# SOC_LOGIC.net
KiCad netlist of a schematic drawn in Altium Designer
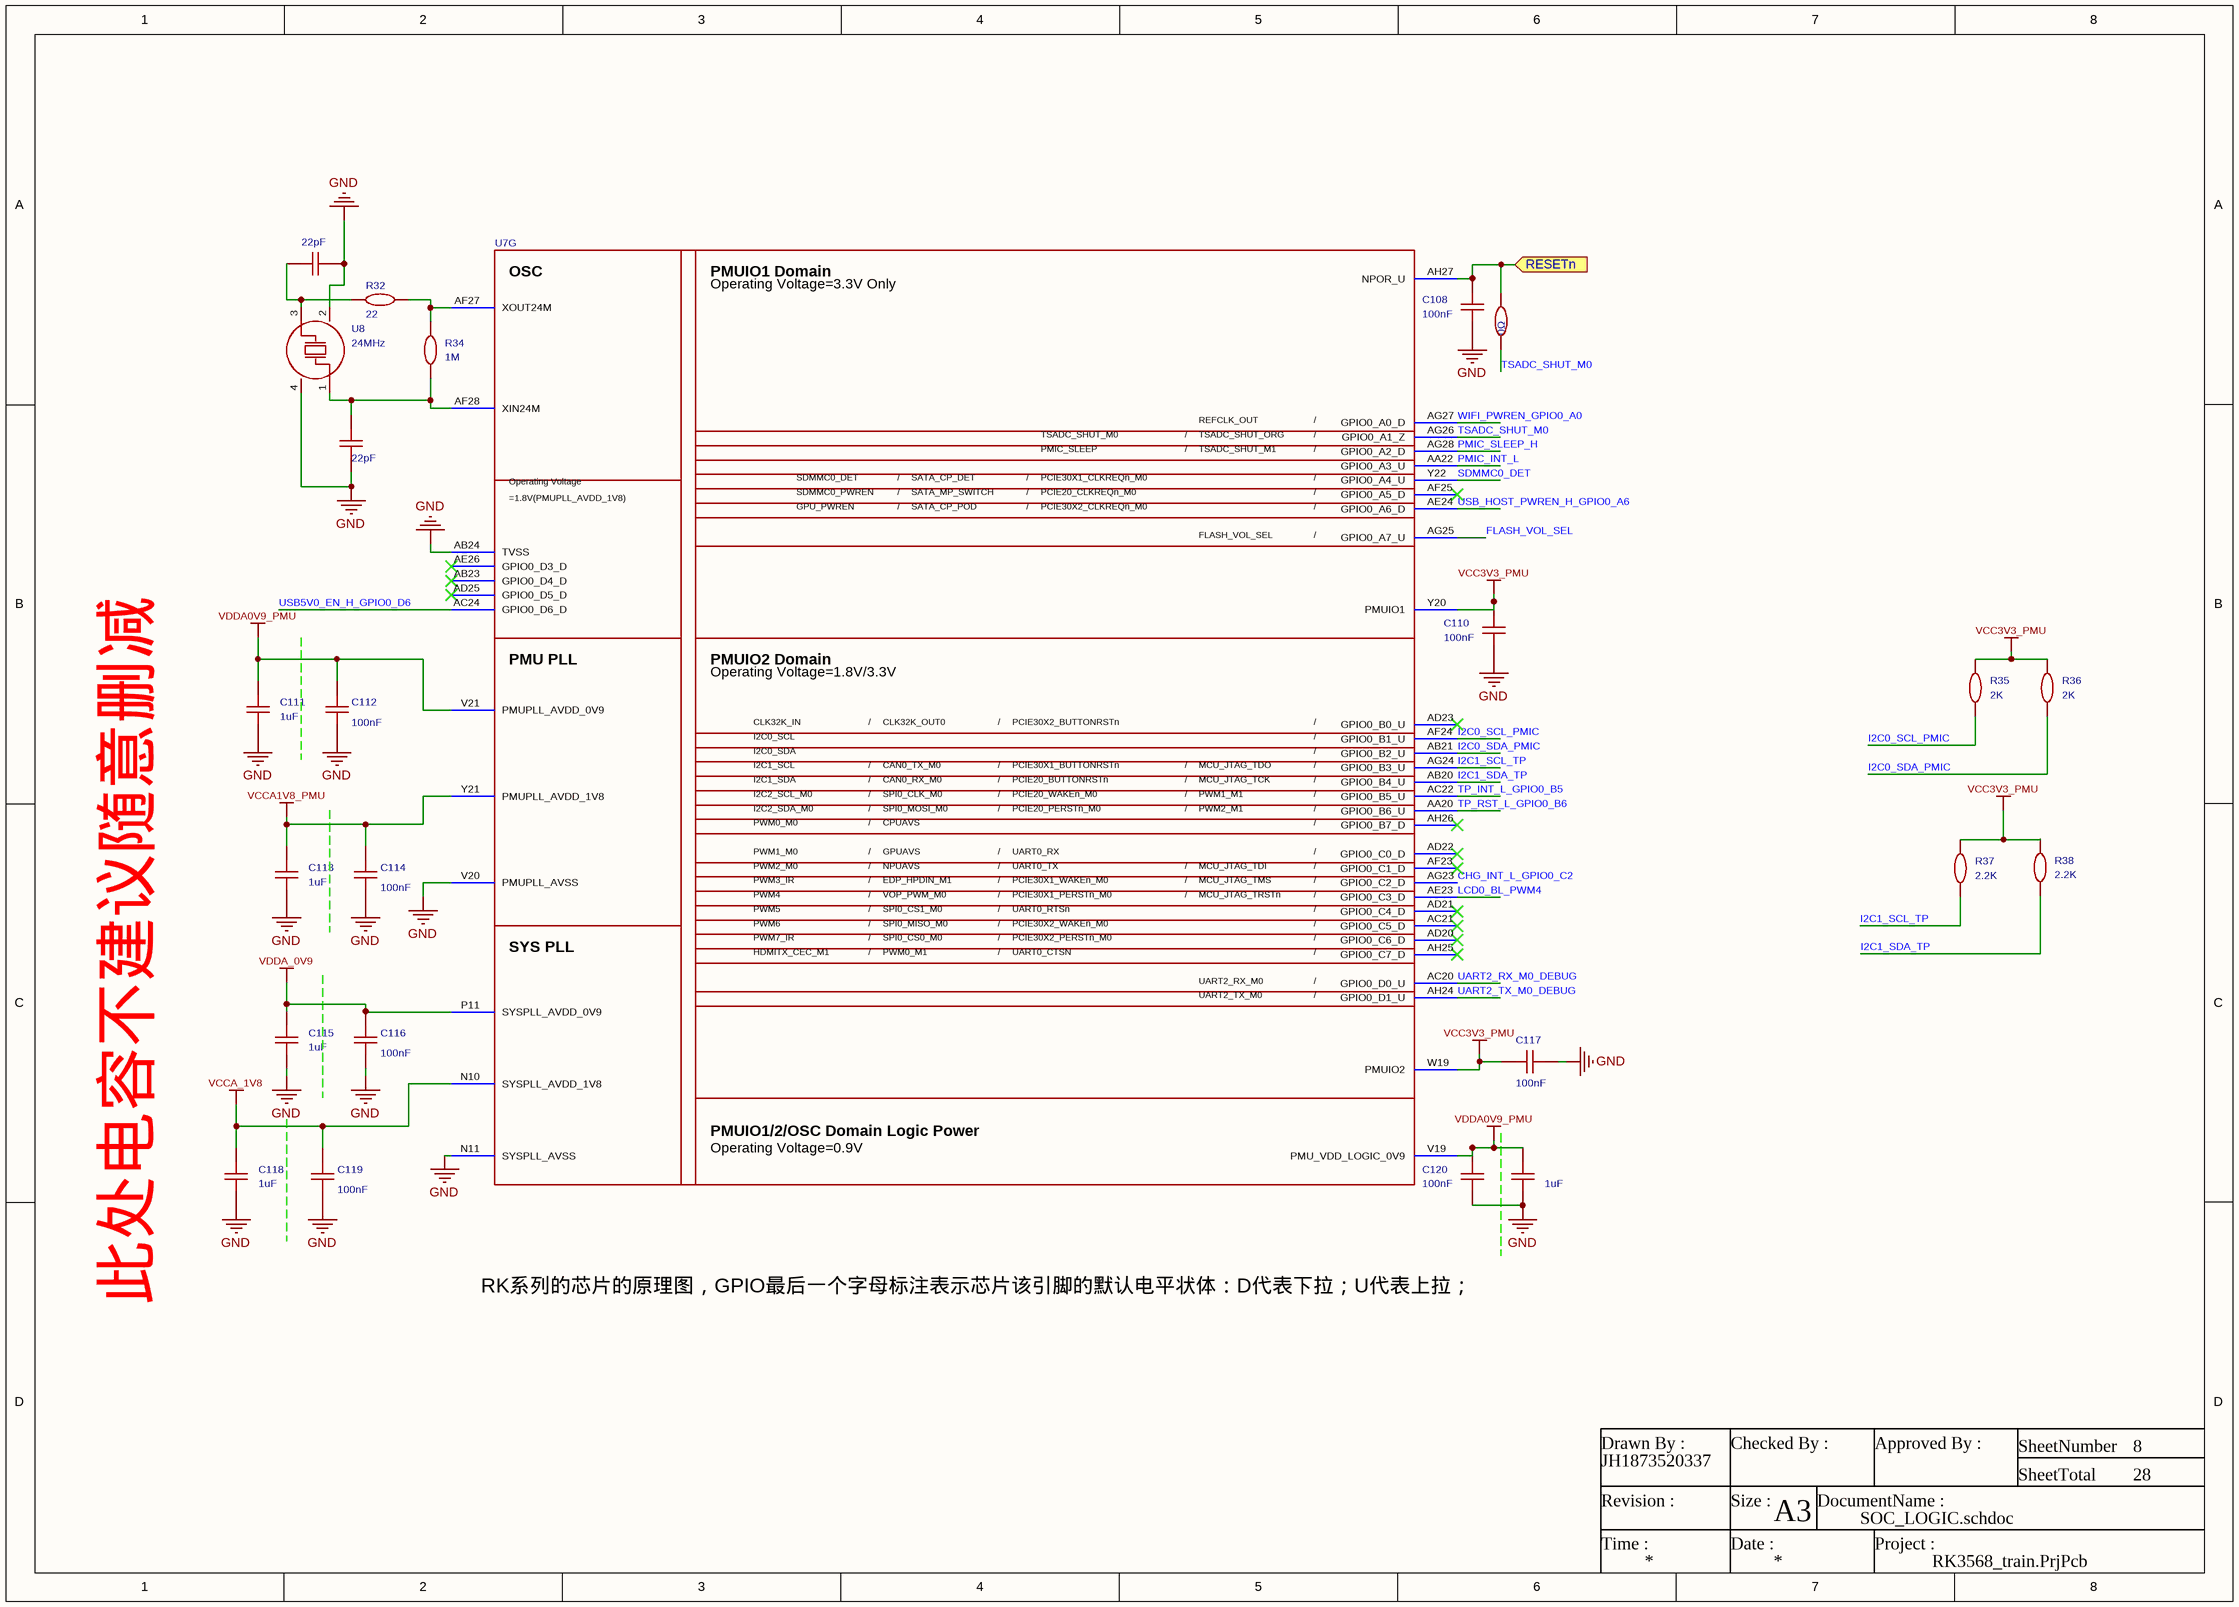
[diagram p0: SOC_LOGIC.schdoc]

(export (version "E")
  (design (tool "Eeschema 10.0.6"))
  (components
    (comp (ref "C107")
      (value "22pF")
      (footprint "MYC0402")
      (description "容值:12pF;精度:±5%;额定电压:50V;材质(温度系数):C0G;")
      (fields (field (name "MANUFACTURER") "SAMSUNG(三星)") (field (name "MANUFACTURERPART") "CL10C120JB8NNNC"))
      (libsource (lib "altium-import") (part "root_0_CL10C120JB8NNNC_"))
    )
    (comp (ref "C108")
      (value "100nF")
      (footprint "C0201")
      (description "容值:4.7uF;精度:±20%;额定电压:6.3V;温度系数:X5R;")
      (fields
        (field (name "MANUFACTURER") "muRata(村田)")
        (field (name "MANUFACTURERPART") "GRM035R60J475ME15D")
      )
      (libsource (lib "altium-import") (part "root_0_GRM035R60J475ME15D_"))
    )
    (comp (ref "C109")
      (value "22pF")
      (footprint "MYC0402")
      (description "容值:12pF;精度:±5%;额定电压:50V;材质(温度系数):C0G;")
      (fields (field (name "MANUFACTURER") "SAMSUNG(三星)") (field (name "MANUFACTURERPART") "CL10C120JB8NNNC"))
      (libsource (lib "altium-import") (part "root_1_CL10C120JB8NNNC_"))
    )
    (comp (ref "C110")
      (value "100nF")
      (footprint "C0201")
      (description "容值:4.7uF;精度:±20%;额定电压:6.3V;温度系数:X5R;")
      (fields
        (field (name "MANUFACTURER") "muRata(村田)")
        (field (name "MANUFACTURERPART") "GRM035R60J475ME15D")
      )
      (libsource (lib "altium-import") (part "root_0_GRM035R60J475ME15D_"))
    )
    (comp (ref "C111")
      (value "1uF")
      (footprint "MYC0402")
      (description "容值:1uF;精度:±10%;额定电压:50V;材质(温度系数):X5R;")
      (fields (field (name "MANUFACTURER") "SAMSUNG(三星)") (field (name "MANUFACTURERPART") "CL10A105KB8NNNC"))
      (libsource (lib "altium-import") (part "root_1_CL10A105KB8NNNC_"))
    )
    (comp (ref "C112")
      (value "100nF")
      (footprint "C0201")
      (description "容值:4.7uF;精度:±20%;额定电压:6.3V;温度系数:X5R;")
      (fields
        (field (name "MANUFACTURER") "muRata(村田)")
        (field (name "MANUFACTURERPART") "GRM035R60J475ME15D")
      )
      (libsource (lib "altium-import") (part "root_0_GRM035R60J475ME15D_"))
    )
    (comp (ref "C113")
      (value "1uF")
      (footprint "MYC0402")
      (description "容值:1uF;精度:±10%;额定电压:50V;材质(温度系数):X5R;")
      (fields (field (name "MANUFACTURER") "SAMSUNG(三星)") (field (name "MANUFACTURERPART") "CL10A105KB8NNNC"))
      (libsource (lib "altium-import") (part "root_1_CL10A105KB8NNNC_"))
    )
    (comp (ref "C114")
      (value "100nF")
      (footprint "C0201")
      (description "容值:4.7uF;精度:±20%;额定电压:6.3V;温度系数:X5R;")
      (fields
        (field (name "MANUFACTURER") "muRata(村田)")
        (field (name "MANUFACTURERPART") "GRM035R60J475ME15D")
      )
      (libsource (lib "altium-import") (part "root_0_GRM035R60J475ME15D_"))
    )
    (comp (ref "C115")
      (value "1uF")
      (footprint "MYC0402")
      (description "容值:100nF;精度:±10%;额定电压:50V;材质(温度系数):X7R;")
      (fields (field (name "MANUFACTURER") "SAMSUNG(三星)") (field (name "MANUFACTURERPART") "CL05B104KB54PNC"))
      (libsource (lib "altium-import") (part "root_1_CL05B104KB54PNC_"))
    )
    (comp (ref "C116")
      (value "100nF")
      (footprint "C0201")
      (description "容值:4.7uF;精度:±20%;额定电压:6.3V;温度系数:X5R;")
      (fields
        (field (name "MANUFACTURER") "muRata(村田)")
        (field (name "MANUFACTURERPART") "GRM035R60J475ME15D")
      )
      (libsource (lib "altium-import") (part "root_0_GRM035R60J475ME15D_"))
    )
    (comp (ref "C117")
      (value "100nF")
      (footprint "C0201")
      (description "容值:4.7uF;精度:±20%;额定电压:6.3V;温度系数:X5R;")
      (fields
        (field (name "MANUFACTURER") "muRata(村田)")
        (field (name "MANUFACTURERPART") "GRM035R60J475ME15D")
      )
      (libsource (lib "altium-import") (part "root_1_GRM035R60J475ME15D_"))
    )
    (comp (ref "C118")
      (value "1uF")
      (footprint "MYC0402")
      (description "容值:100nF;精度:±10%;额定电压:50V;材质(温度系数):X7R;")
      (fields (field (name "MANUFACTURER") "YAGEO(国巨)") (field (name "MANUFACTURERPART") "CC0603KRX7R9BB104"))
      (libsource (lib "altium-import") (part "root_1_CC0603KRX7R9BB104_"))
    )
    (comp (ref "C119")
      (value "100nF")
      (footprint "C0201")
      (description "容值:4.7uF;精度:±20%;额定电压:6.3V;温度系数:X5R;")
      (fields
        (field (name "MANUFACTURER") "muRata(村田)")
        (field (name "MANUFACTURERPART") "GRM035R60J475ME15D")
      )
      (libsource (lib "altium-import") (part "root_0_GRM035R60J475ME15D_"))
    )
    (comp (ref "C120")
      (value "100nF")
      (footprint "C0201")
      (description "容值:4.7uF;精度:±20%;额定电压:6.3V;温度系数:X5R;")
      (fields
        (field (name "MANUFACTURER") "muRata(村田)")
        (field (name "MANUFACTURERPART") "GRM035R60J475ME15D")
      )
      (libsource (lib "altium-import") (part "root_2_GRM035R60J475ME15D_"))
    )
    (comp (ref "C121")
      (value "1uF")
      (footprint "MYC0402")
      (description "容值:1uF;精度:±10%;额定电压:50V;材质(温度系数):X5R;")
      (fields (field (name "MANUFACTURER") "SAMSUNG(三星)") (field (name "MANUFACTURERPART") "CL10A105KB8NNNC"))
      (libsource (lib "altium-import") (part "root_1_CL10A105KB8NNNC_"))
    )
    (comp (ref "R32")
      (value "22")
      (footprint "R0402")
      (libsource (lib "altium-import") (part "root_0_Res_0402_"))
    )
    (comp (ref "R33")
      (value "0Ω")
      (footprint "r0402-nsk")
      (description "电阻类型:厚膜电阻;阻值:0Ω;精度:±1%;功率:62.5mW;")
      (fields
        (field (name "MANUFACTURER") "UNI-ROYAL(厚声)")
        (field (name "MANUFACTURERPART") "0402WGF0000TCE")
      )
      (libsource (lib "altium-import") (part "root_1_0402WGF0000TCE_"))
    )
    (comp (ref "R34")
      (value "1M")
      (footprint "R0402")
      (libsource (lib "altium-import") (part "root_1_Res_0402_"))
    )
    (comp (ref "R35")
      (value "2K")
      (footprint "R0402")
      (libsource (lib "altium-import") (part "root_1_Res_0402_"))
    )
    (comp (ref "R36")
      (value "2K")
      (footprint "R0402")
      (libsource (lib "altium-import") (part "root_1_Res_0402_"))
    )
    (comp (ref "R37")
      (value "2.2K")
      (footprint "R0402")
      (libsource (lib "altium-import") (part "root_1_Res_0402_"))
    )
    (comp (ref "R38")
      (value "2.2K")
      (footprint "R0402")
      (libsource (lib "altium-import") (part "root_1_Res_0402_"))
    )
    (comp (ref "U7")
      (value "RK3568")
      (footprint "BGA-636_L19.0-W19.0-P0.65-BL")
      (libsource (lib "altium-import") (part "root_0_RK3568_"))
    )
    (comp (ref "U8")
      (value "24MHz")
      (footprint "CRYSTAL-SMD_4P-L3.2-W2.5-BL")
      (description "频率:24MHz;常温频差:±10ppm;外接负载电容:12pF;频率稳定度(全温):±30ppm;")
      (fields
        (field (name "MANUFACTURER") "SST(索斯特)")
        (field (name "MANUFACTURERPART") "3225 24M 12PF 10PPM")
      )
      (libsource (lib "altium-import") (part "root_1_3225 24M 12PF 10PPM_"))
    )
  )
  (nets
    (net (code "1") (name "/CHG_INT_L_GPIO0_C2") (class "Default")
      (node (ref "U7") (pin "AG23") (pinfunction "GPIO0_C2_D_AG23") (pintype "passive"))
    )
    (net (code "2") (name "/FLASH_VOL_SEL") (class "Default")
      (node (ref "U7") (pin "AG25") (pinfunction "GPIO0_A7_U_AG25") (pintype "passive"))
    )
    (net (code "3") (name "/I2C0_SCL_PMIC") (class "Default")
      (node (ref "R35") (pin "1") (pinfunction "1_1") (pintype "passive"))
      (node (ref "U7") (pin "AF24") (pinfunction "GPIO0_B1_U_AF24") (pintype "passive"))
    )
    (net (code "4") (name "/I2C0_SDA_PMIC") (class "Default")
      (node (ref "R36") (pin "1") (pinfunction "1_1") (pintype "passive"))
      (node (ref "U7") (pin "AB21") (pinfunction "GPIO0_B2_U_AB21") (pintype "passive"))
    )
    (net (code "5") (name "/I2C1_SCL_TP") (class "Default")
      (node (ref "R37") (pin "1") (pinfunction "1_1") (pintype "passive"))
      (node (ref "U7") (pin "AG24") (pinfunction "GPIO0_B3_U_AG24") (pintype "passive"))
    )
    (net (code "6") (name "/I2C1_SDA_TP") (class "Default")
      (node (ref "R38") (pin "1") (pinfunction "1_1") (pintype "passive"))
      (node (ref "U7") (pin "AB20") (pinfunction "GPIO0_B4_U_AB20") (pintype "passive"))
    )
    (net (code "7") (name "/LCD0_BL_PWM4") (class "Default")
      (node (ref "U7") (pin "AE23") (pinfunction "GPIO0_C3_D_AE23") (pintype "passive"))
    )
    (net (code "8") (name "/PMIC_INT_L") (class "Default")
      (node (ref "U7") (pin "AA22") (pinfunction "GPIO0_A3_U_AA22") (pintype "passive"))
    )
    (net (code "9") (name "/PMIC_SLEEP_H") (class "Default")
      (node (ref "U7") (pin "AG28") (pinfunction "GPIO0_A2_D_AG28") (pintype "passive"))
    )
    (net (code "10") (name "/RESETn") (class "Default")
      (node (ref "C108") (pin "2") (pinfunction "2_2") (pintype "passive"))
      (node (ref "R33") (pin "2") (pinfunction "2_2") (pintype "passive"))
      (node (ref "U7") (pin "AH27") (pinfunction "NPOR_U_AH27") (pintype "passive"))
    )
    (net (code "11") (name "/SDMMC0_DET") (class "Default")
      (node (ref "U7") (pin "Y22") (pinfunction "GPIO0_A4_U_Y22") (pintype "passive"))
    )
    (net (code "12") (name "/TP_INT_L_GPIO0_B5") (class "Default")
      (node (ref "U7") (pin "AC22") (pinfunction "GPIO0_B5_U_AC22") (pintype "passive"))
    )
    (net (code "13") (name "/TP_RST_L_GPIO0_B6") (class "Default")
      (node (ref "U7") (pin "AA20") (pinfunction "GPIO0_B6_U_AA20") (pintype "passive"))
    )
    (net (code "14") (name "/TSADC_SHUT_M0") (class "Default")
      (node (ref "R33") (pin "1") (pinfunction "1_1") (pintype "passive"))
      (node (ref "U7") (pin "AG26") (pinfunction "GPIO0_A1_Z_AG26") (pintype "passive"))
    )
    (net (code "15") (name "/UART2_RX_M0_DEBUG") (class "Default")
      (node (ref "U7") (pin "AC20") (pinfunction "GPIO0_D0_U_AC20") (pintype "passive"))
    )
    (net (code "16") (name "/UART2_TX_M0_DEBUG") (class "Default")
      (node (ref "U7") (pin "AH24") (pinfunction "GPIO0_D1_U_AH24") (pintype "passive"))
    )
    (net (code "17") (name "/USB5V0_EN_H_GPIO0_D6") (class "Default")
      (node (ref "U7") (pin "AC24") (pinfunction "GPIO0_D6_D_AC24") (pintype "passive"))
    )
    (net (code "18") (name "/USB_HOST_PWREN_H_GPIO0_A6") (class "Default")
      (node (ref "U7") (pin "AE24") (pinfunction "GPIO0_A6_D_AE24") (pintype "passive"))
    )
    (net (code "19") (name "/WIFI_PWREN_GPIO0_A0") (class "Default")
      (node (ref "U7") (pin "AG27") (pinfunction "GPIO0_A0_D_AG27") (pintype "passive"))
    )
    (net (code "20") (name "GND") (class "Default")
      (node (ref "C107") (pin "2") (pinfunction "2_2") (pintype "passive"))
      (node (ref "C108") (pin "1") (pinfunction "1_1") (pintype "passive"))
      (node (ref "C109") (pin "1") (pinfunction "1_1") (pintype "passive"))
      (node (ref "C110") (pin "1") (pinfunction "1_1") (pintype "passive"))
      (node (ref "C111") (pin "1") (pinfunction "1_1") (pintype "passive"))
      (node (ref "C112") (pin "1") (pinfunction "1_1") (pintype "passive"))
      (node (ref "C113") (pin "1") (pinfunction "1_1") (pintype "passive"))
      (node (ref "C114") (pin "1") (pinfunction "1_1") (pintype "passive"))
      (node (ref "C115") (pin "1") (pinfunction "1_1") (pintype "passive"))
      (node (ref "C116") (pin "1") (pinfunction "1_1") (pintype "passive"))
      (node (ref "C117") (pin "1") (pinfunction "1_1") (pintype "passive"))
      (node (ref "C118") (pin "1") (pinfunction "1_1") (pintype "passive"))
      (node (ref "C119") (pin "1") (pinfunction "1_1") (pintype "passive"))
      (node (ref "C120") (pin "2") (pinfunction "2_2") (pintype "passive"))
      (node (ref "C121") (pin "1") (pinfunction "1_1") (pintype "passive"))
      (node (ref "U7") (pin "AB24") (pinfunction "TVSS_AB24") (pintype "passive"))
      (node (ref "U7") (pin "N11") (pinfunction "SYSPLL_AVSS_N11") (pintype "passive"))
      (node (ref "U7") (pin "V20") (pinfunction "PMUPLL_AVSS_V20") (pintype "passive"))
      (node (ref "U8") (pin "2") (pinfunction "GND_2") (pintype "passive"))
      (node (ref "U8") (pin "4") (pinfunction "GND_4") (pintype "passive"))
    )
    (net (code "21") (name "Net-(U7G-XIN24M)") (class "Default")
      (node (ref "C109") (pin "2") (pinfunction "2_2") (pintype "passive"))
      (node (ref "R34") (pin "1") (pinfunction "1_1") (pintype "passive"))
      (node (ref "U7") (pin "AF28") (pinfunction "XIN24M_AF28") (pintype "passive"))
      (node (ref "U8") (pin "1") (pinfunction "OSC1_1") (pintype "passive"))
    )
    (net (code "22") (name "Net-(U7G-XOUT24M)") (class "Default")
      (node (ref "R32") (pin "2") (pinfunction "2_2") (pintype "passive"))
      (node (ref "R34") (pin "2") (pinfunction "2_2") (pintype "passive"))
      (node (ref "U7") (pin "AF27") (pinfunction "XOUT24M_AF27") (pintype "passive"))
    )
    (net (code "23") (name "Net-(U8-OSC2)") (class "Default")
      (node (ref "C107") (pin "1") (pinfunction "1_1") (pintype "passive"))
      (node (ref "R32") (pin "1") (pinfunction "1_1") (pintype "passive"))
      (node (ref "U8") (pin "3") (pinfunction "OSC2_3") (pintype "passive"))
    )
    (net (code "24") (name "VCC3V3_PMU") (class "Default")
      (node (ref "C110") (pin "2") (pinfunction "2_2") (pintype "passive"))
      (node (ref "C117") (pin "2") (pinfunction "2_2") (pintype "passive"))
      (node (ref "R35") (pin "2") (pinfunction "2_2") (pintype "passive"))
      (node (ref "R36") (pin "2") (pinfunction "2_2") (pintype "passive"))
      (node (ref "R37") (pin "2") (pinfunction "2_2") (pintype "passive"))
      (node (ref "R38") (pin "2") (pinfunction "2_2") (pintype "passive"))
      (node (ref "U7") (pin "W19") (pinfunction "PMUIO2_W19") (pintype "passive"))
      (node (ref "U7") (pin "Y20") (pinfunction "PMUIO1_Y20") (pintype "passive"))
    )
    (net (code "25") (name "VCCA1V8_PMU") (class "Default")
      (node (ref "C113") (pin "2") (pinfunction "2_2") (pintype "passive"))
      (node (ref "C114") (pin "2") (pinfunction "2_2") (pintype "passive"))
      (node (ref "U7") (pin "Y21") (pinfunction "PMUPLL_AVDD_1V8_Y21") (pintype "passive"))
    )
    (net (code "26") (name "VCCA_1V8") (class "Default")
      (node (ref "C118") (pin "2") (pinfunction "2_2") (pintype "passive"))
      (node (ref "C119") (pin "2") (pinfunction "2_2") (pintype "passive"))
      (node (ref "U7") (pin "N10") (pinfunction "SYSPLL_AVDD_1V8_N10") (pintype "passive"))
    )
    (net (code "27") (name "VDDA0V9_PMU") (class "Default")
      (node (ref "C111") (pin "2") (pinfunction "2_2") (pintype "passive"))
      (node (ref "C112") (pin "2") (pinfunction "2_2") (pintype "passive"))
      (node (ref "C120") (pin "1") (pinfunction "1_1") (pintype "passive"))
      (node (ref "C121") (pin "2") (pinfunction "2_2") (pintype "passive"))
      (node (ref "U7") (pin "V19") (pinfunction "PMU_VDD_LOGIC_0V9_V19") (pintype "passive"))
      (node (ref "U7") (pin "V21") (pinfunction "PMUPLL_AVDD_0V9_V21") (pintype "passive"))
    )
    (net (code "28") (name "VDDA_0V9") (class "Default")
      (node (ref "C115") (pin "2") (pinfunction "2_2") (pintype "passive"))
      (node (ref "C116") (pin "2") (pinfunction "2_2") (pintype "passive"))
      (node (ref "U7") (pin "P11") (pinfunction "SYSPLL_AVDD_0V9_P11") (pintype "passive"))
    )
    (net (code "29") (name "unconnected-(U7G-GPIO0_A5_D-PadAF25)") (class "Default")
      (node (ref "U7") (pin "AF25") (pinfunction "GPIO0_A5_D_AF25") (pintype "passive+no_connect"))
    )
    (net (code "30") (name "unconnected-(U7G-GPIO0_B0_U-PadAD23)") (class "Default")
      (node (ref "U7") (pin "AD23") (pinfunction "GPIO0_B0_U_AD23") (pintype "passive+no_connect"))
    )
    (net (code "31") (name "unconnected-(U7G-GPIO0_B7_D-PadAH26)") (class "Default")
      (node (ref "U7") (pin "AH26") (pinfunction "GPIO0_B7_D_AH26") (pintype "passive+no_connect"))
    )
    (net (code "32") (name "unconnected-(U7G-GPIO0_C0_D-PadAD22)") (class "Default")
      (node (ref "U7") (pin "AD22") (pinfunction "GPIO0_C0_D_AD22") (pintype "passive+no_connect"))
    )
    (net (code "33") (name "unconnected-(U7G-GPIO0_C1_D-PadAF23)") (class "Default")
      (node (ref "U7") (pin "AF23") (pinfunction "GPIO0_C1_D_AF23") (pintype "passive+no_connect"))
    )
    (net (code "34") (name "unconnected-(U7G-GPIO0_C4_D-PadAD21)") (class "Default")
      (node (ref "U7") (pin "AD21") (pinfunction "GPIO0_C4_D_AD21") (pintype "passive+no_connect"))
    )
    (net (code "35") (name "unconnected-(U7G-GPIO0_C5_D-PadAC21)") (class "Default")
      (node (ref "U7") (pin "AC21") (pinfunction "GPIO0_C5_D_AC21") (pintype "passive+no_connect"))
    )
    (net (code "36") (name "unconnected-(U7G-GPIO0_C6_D-PadAD20)") (class "Default")
      (node (ref "U7") (pin "AD20") (pinfunction "GPIO0_C6_D_AD20") (pintype "passive+no_connect"))
    )
    (net (code "37") (name "unconnected-(U7G-GPIO0_C7_D-PadAH25)") (class "Default")
      (node (ref "U7") (pin "AH25") (pinfunction "GPIO0_C7_D_AH25") (pintype "passive+no_connect"))
    )
    (net (code "38") (name "unconnected-(U7G-GPIO0_D3_D-PadAE26)") (class "Default")
      (node (ref "U7") (pin "AE26") (pinfunction "GPIO0_D3_D_AE26") (pintype "passive+no_connect"))
    )
    (net (code "39") (name "unconnected-(U7G-GPIO0_D4_D-PadAB23)") (class "Default")
      (node (ref "U7") (pin "AB23") (pinfunction "GPIO0_D4_D_AB23") (pintype "passive+no_connect"))
    )
    (net (code "40") (name "unconnected-(U7G-GPIO0_D5_D-PadAD25)") (class "Default")
      (node (ref "U7") (pin "AD25") (pinfunction "GPIO0_D5_D_AD25") (pintype "passive+no_connect"))
    )
  )
)
